# ps2_interface.net
KiCad netlist of a schematic drawn in Altium Designer
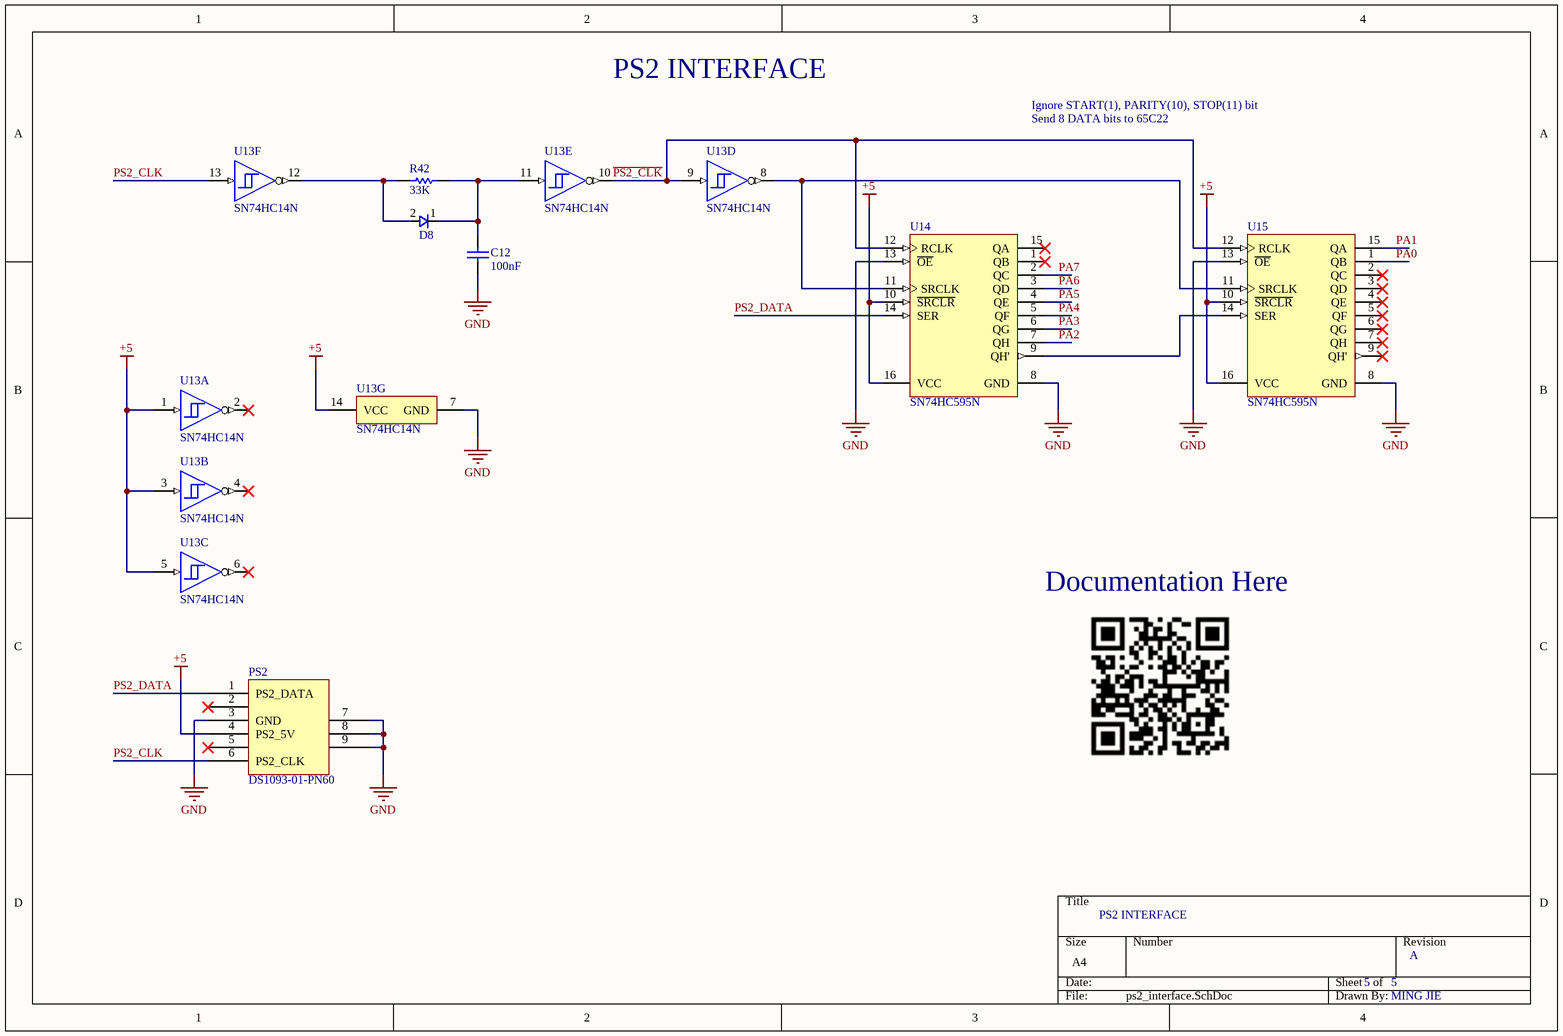
[diagram p0: ps2_interface.SchDoc]

(export (version "E")
  (design (tool "Eeschema 10.0.6"))
  (components
    (comp (ref "C12")
      (value "GRM21BR71H104KA01L")
      (footprint "CAPC2013X135X45ML10T25")
      (description "Chip Capacitor, 0.1 uF, +/- 10%, 50 V, -55 to 125 degC, 0805 (2012 Metric), RoHS, Tape and Reel")
      (fields
        (field (name "VOLTAGE") "50V")
        (field (name "CAPACITANCE") "100nF")
        (field (name "TOLERANCE") "10%")
      )
      (libsource (lib "Altium Content Vault") (part "CAP-NP-2"))
    )
    (comp (ref "D8")
      (value "Diode, General Purpose")
      (footprint "DO-214AC/SMA")
      (description "General Purpose Diode, SMT, DO-214")
      (libsource (lib "6502_lib") (part "C95872"))
    )
    (comp (ref "PS2")
      (value "DS1093-01-PN60")
      (footprint "PS2_PORT")
      (description "PS2 Port")
      (libsource (lib "6502_lib") (part "PS2_CONN"))
    )
    (comp (ref "R42")
      (value "0805W8F3302T5E")
      (footprint "RESC2013X50X30NL20T20")
      (description "33K, 0805 Chip Resistor, UniOhm")
      (fields (field (name "MANUFACTURER") "Uni Ohm") (field (name "RESISTANCE") "33K"))
      (libsource (lib "Altium Content Vault") (part "RES"))
    )
    (comp (ref "U13")
      (value "SN74HC14N")
      (footprint "N0014A")
      (description "Hex Schmitt-Trigger Inverters, N0014A, TUBE")
      (fields
        (field (name "MANUFACTURER") "Texas Instruments")
        (field (name "GENERIC PART NUMBER") "SN74HC14")
      )
      (libsource (lib "Altium Content Vault") (part "TI-CD_SNX4XXXXXX4X_19A-14-SCHMITT"))
    )
    (comp (ref "U14")
      (value "SN74HC595N")
      (footprint "N0016A")
      (description "8-Bit Shift Registers With 3-State Output Registers, N0016A, TUBE")
      (fields
        (field (name "GENERIC PART NUMBER") "SN74HC595")
        (field (name "MANUFACTURER") "Texas Instruments")
      )
      (libsource (lib "Altium Content Vault") (part "TI-SN74XHCT595X_SN74LV595A-16"))
    )
    (comp (ref "U15")
      (value "SN74HC595N")
      (footprint "N0016A")
      (description "8-Bit Shift Registers With 3-State Output Registers, N0016A, TUBE")
      (fields
        (field (name "GENERIC PART NUMBER") "SN74HC595")
        (field (name "MANUFACTURER") "Texas Instruments")
      )
      (libsource (lib "Altium Content Vault") (part "TI-SN74XHCT595X_SN74LV595A-16"))
    )
  )
  (nets
    (net (code "1") (name "+5") (class "Default")
      (node (ref "PS2") (pin "4") (pinfunction "PS2_5V_4") (pintype "passive"))
      (node (ref "U13") (pin "1") (pinfunction "1A_1") (pintype "input"))
      (node (ref "U13") (pin "14") (pinfunction "VCC_14") (pintype "power_in"))
      (node (ref "U13") (pin "3") (pinfunction "2A_3") (pintype "input"))
      (node (ref "U13") (pin "5") (pinfunction "3A_5") (pintype "input"))
      (node (ref "U14") (pin "10") (pinfunction "~{SRCLR}_10") (pintype "input"))
      (node (ref "U14") (pin "16") (pinfunction "VCC_16") (pintype "power_in"))
      (node (ref "U15") (pin "10") (pinfunction "~{SRCLR}_10") (pintype "input"))
      (node (ref "U15") (pin "16") (pinfunction "VCC_16") (pintype "power_in"))
    )
    (net (code "2") (name "/PA0") (class "Default")
      (node (ref "U15") (pin "1") (pinfunction "QB_1") (pintype "tri_state"))
    )
    (net (code "3") (name "/PA1") (class "Default")
      (node (ref "U15") (pin "15") (pinfunction "QA_15") (pintype "tri_state"))
    )
    (net (code "4") (name "/PA2") (class "Default")
      (node (ref "U14") (pin "7") (pinfunction "QH_7") (pintype "tri_state"))
    )
    (net (code "5") (name "/PA3") (class "Default")
      (node (ref "U14") (pin "6") (pinfunction "QG_6") (pintype "tri_state"))
    )
    (net (code "6") (name "/PA4") (class "Default")
      (node (ref "U14") (pin "5") (pinfunction "QF_5") (pintype "tri_state"))
    )
    (net (code "7") (name "/PA5") (class "Default")
      (node (ref "U14") (pin "4") (pinfunction "QE_4") (pintype "tri_state"))
    )
    (net (code "8") (name "/PA6") (class "Default")
      (node (ref "U14") (pin "3") (pinfunction "QD_3") (pintype "tri_state"))
    )
    (net (code "9") (name "/PA7") (class "Default")
      (node (ref "U14") (pin "2") (pinfunction "QC_2") (pintype "tri_state"))
    )
    (net (code "10") (name "/PS2_CLK") (class "Default")
      (node (ref "PS2") (pin "6") (pinfunction "PS2_CLK_6") (pintype "passive"))
      (node (ref "U13") (pin "13") (pinfunction "6A_13") (pintype "input"))
    )
    (net (code "11") (name "/PS2_DATA") (class "Default")
      (node (ref "PS2") (pin "1") (pinfunction "PS2_DATA_1") (pintype "passive"))
      (node (ref "U14") (pin "14") (pinfunction "SER_14") (pintype "input"))
    )
    (net (code "12") (name "/~{PS2_CLK}") (class "Default")
      (node (ref "U13") (pin "10") (pinfunction "~{5Y}_10") (pintype "output"))
      (node (ref "U13") (pin "9") (pinfunction "4A_9") (pintype "input"))
      (node (ref "U14") (pin "12") (pinfunction "RCLK_12") (pintype "input"))
      (node (ref "U15") (pin "12") (pinfunction "RCLK_12") (pintype "input"))
    )
    (net (code "13") (name "GND") (class "Default")
      (node (ref "C12") (pin "2") (pinfunction "2_2") (pintype "passive"))
      (node (ref "PS2") (pin "3") (pinfunction "GND_3") (pintype "passive"))
      (node (ref "PS2") (pin "7") (pinfunction "7_7") (pintype "passive"))
      (node (ref "PS2") (pin "8") (pinfunction "8_8") (pintype "passive"))
      (node (ref "PS2") (pin "9") (pinfunction "9_9") (pintype "passive"))
      (node (ref "U13") (pin "7") (pinfunction "GND_7") (pintype "power_in"))
      (node (ref "U14") (pin "13") (pinfunction "~{OE}_13") (pintype "input"))
      (node (ref "U14") (pin "8") (pinfunction "GND_8") (pintype "power_in"))
      (node (ref "U15") (pin "13") (pinfunction "~{OE}_13") (pintype "input"))
      (node (ref "U15") (pin "8") (pinfunction "GND_8") (pintype "power_in"))
    )
    (net (code "14") (name "Net-(U13D-~{4Y})") (class "Default")
      (node (ref "U13") (pin "8") (pinfunction "~{4Y}_8") (pintype "output"))
      (node (ref "U14") (pin "11") (pinfunction "SRCLK_11") (pintype "input"))
      (node (ref "U15") (pin "11") (pinfunction "SRCLK_11") (pintype "input"))
    )
    (net (code "15") (name "Net-(U13E-5A)") (class "Default")
      (node (ref "C12") (pin "1") (pinfunction "1_1") (pintype "passive"))
      (node (ref "D8") (pin "1") (pinfunction "1_1") (pintype "passive"))
      (node (ref "R42") (pin "2") (pinfunction "2_2") (pintype "passive"))
      (node (ref "U13") (pin "11") (pinfunction "5A_11") (pintype "input"))
    )
    (net (code "16") (name "Net-(U13F-~{6Y})") (class "Default")
      (node (ref "D8") (pin "2") (pinfunction "2_2") (pintype "passive"))
      (node (ref "R42") (pin "1") (pinfunction "1_1") (pintype "passive"))
      (node (ref "U13") (pin "12") (pinfunction "~{6Y}_12") (pintype "output"))
    )
    (net (code "17") (name "Net-(U14-QH')") (class "Default")
      (node (ref "U14") (pin "9") (pinfunction "QH'_9") (pintype "output"))
      (node (ref "U15") (pin "14") (pinfunction "SER_14") (pintype "input"))
    )
    (net (code "18") (name "unconnected-(PS2-Pad2)") (class "Default")
      (node (ref "PS2") (pin "2") (pinfunction "2_2") (pintype "passive+no_connect"))
    )
    (net (code "19") (name "unconnected-(PS2-Pad5)") (class "Default")
      (node (ref "PS2") (pin "5") (pinfunction "5_5") (pintype "passive+no_connect"))
    )
    (net (code "20") (name "unconnected-(U13A-~{1Y}-Pad2)") (class "Default")
      (node (ref "U13") (pin "2") (pinfunction "~{1Y}_2") (pintype "output+no_connect"))
    )
    (net (code "21") (name "unconnected-(U13B-~{2Y}-Pad4)") (class "Default")
      (node (ref "U13") (pin "4") (pinfunction "~{2Y}_4") (pintype "output+no_connect"))
    )
    (net (code "22") (name "unconnected-(U13C-~{3Y}-Pad6)") (class "Default")
      (node (ref "U13") (pin "6") (pinfunction "~{3Y}_6") (pintype "output+no_connect"))
    )
    (net (code "23") (name "unconnected-(U14-QA-Pad15)") (class "Default")
      (node (ref "U14") (pin "15") (pinfunction "QA_15") (pintype "tri_state+no_connect"))
    )
    (net (code "24") (name "unconnected-(U14-QB-Pad1)") (class "Default")
      (node (ref "U14") (pin "1") (pinfunction "QB_1") (pintype "tri_state+no_connect"))
    )
    (net (code "25") (name "unconnected-(U15-QC-Pad2)") (class "Default")
      (node (ref "U15") (pin "2") (pinfunction "QC_2") (pintype "tri_state+no_connect"))
    )
    (net (code "26") (name "unconnected-(U15-QD-Pad3)") (class "Default")
      (node (ref "U15") (pin "3") (pinfunction "QD_3") (pintype "tri_state+no_connect"))
    )
    (net (code "27") (name "unconnected-(U15-QE-Pad4)") (class "Default")
      (node (ref "U15") (pin "4") (pinfunction "QE_4") (pintype "tri_state+no_connect"))
    )
    (net (code "28") (name "unconnected-(U15-QF-Pad5)") (class "Default")
      (node (ref "U15") (pin "5") (pinfunction "QF_5") (pintype "tri_state+no_connect"))
    )
    (net (code "29") (name "unconnected-(U15-QG-Pad6)") (class "Default")
      (node (ref "U15") (pin "6") (pinfunction "QG_6") (pintype "tri_state+no_connect"))
    )
    (net (code "30") (name "unconnected-(U15-QH'-Pad9)") (class "Default")
      (node (ref "U15") (pin "9") (pinfunction "QH'_9") (pintype "output+no_connect"))
    )
    (net (code "31") (name "unconnected-(U15-QH-Pad7)") (class "Default")
      (node (ref "U15") (pin "7") (pinfunction "QH_7") (pintype "tri_state+no_connect"))
    )
  )
)
